# PG04_Communications.net
KiCad netlist of a schematic drawn in Altium Designer
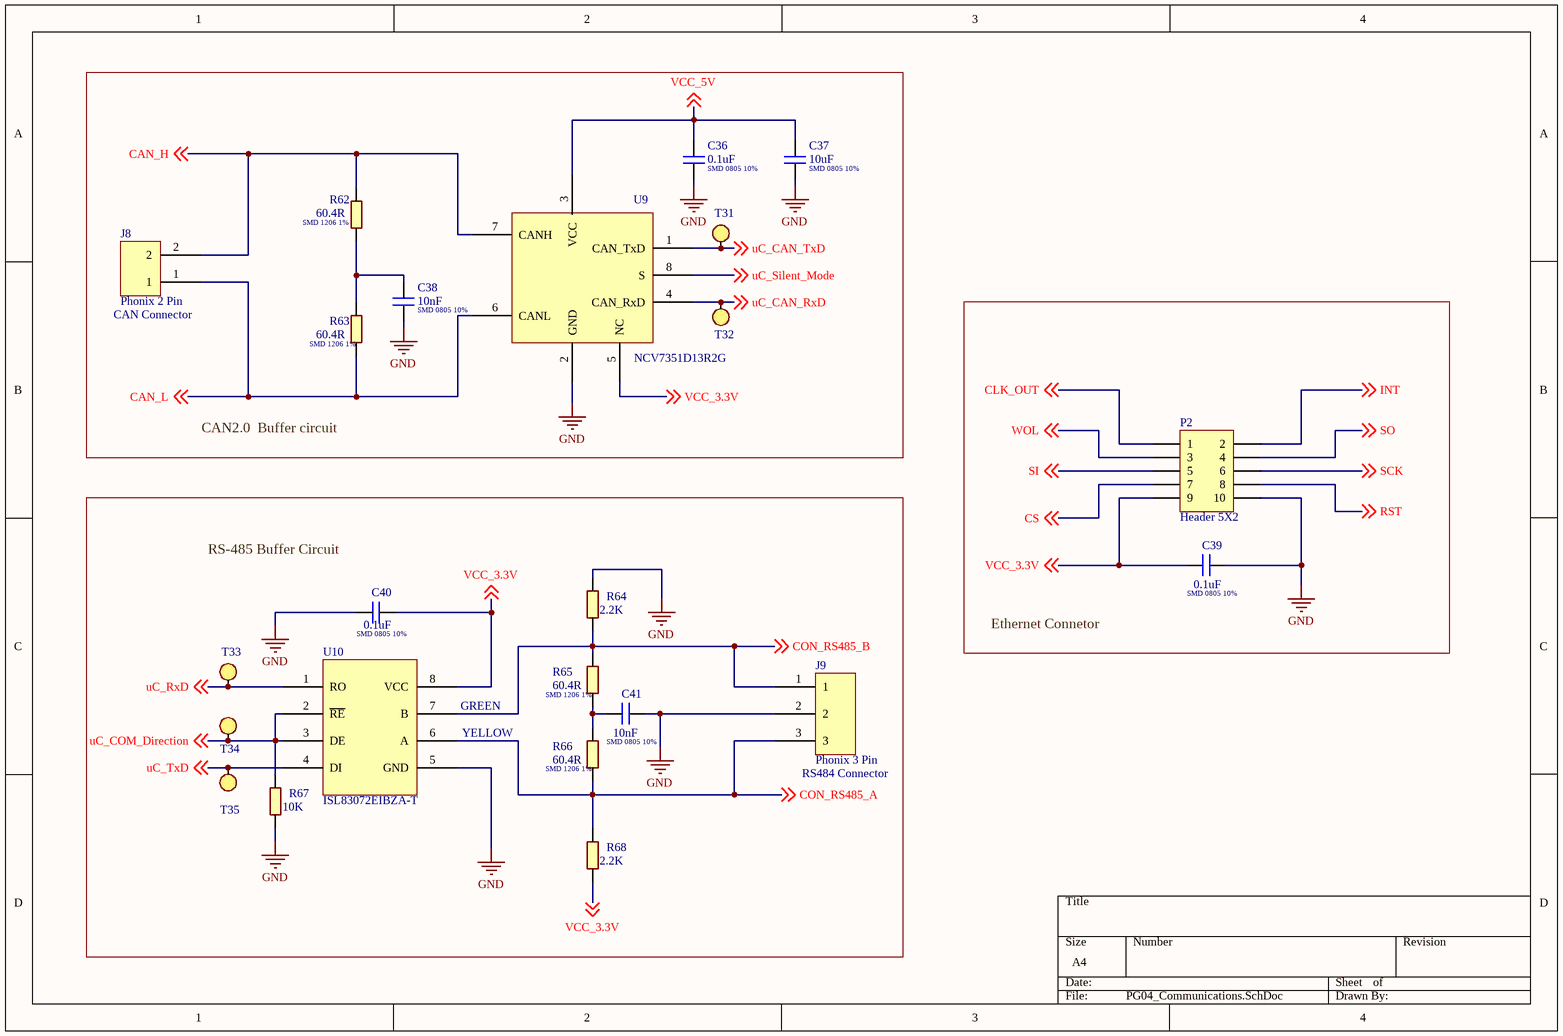
[diagram p0: PG04_Communications.SchDoc]

(export (version "E")
  (design (tool "Eeschema 10.0.6"))
  (components
    (comp (ref "C36")
      (value "SMD 0805 10%")
      (footprint "SMD0805")
      (fields (field (name "MANUFACTURER") "Vishay") (field (name "ALTIUM_VALUE") "0.1uF"))
      (libsource (lib "Schlib1") (part "CAP_SMD"))
    )
    (comp (ref "C37")
      (value "SMD 0805 10%")
      (footprint "SMD0805")
      (fields (field (name "MANUFACTURER") "Vishay") (field (name "ALTIUM_VALUE") "10uF"))
      (libsource (lib "Schlib1") (part "CAP_SMD"))
    )
    (comp (ref "C38")
      (value "SMD 0805 10%")
      (footprint "SMD0805")
      (fields (field (name "MANUFACTURER") "Vishay") (field (name "ALTIUM_VALUE") "10nF"))
      (libsource (lib "Schlib1") (part "CAP_SMD"))
    )
    (comp (ref "C39")
      (value "SMD 0805 10%")
      (footprint "SMD0805")
      (fields (field (name "MANUFACTURER") "Vishay") (field (name "ALTIUM_VALUE") "0.1uF"))
      (libsource (lib "Schlib1") (part "CAP_SMD"))
    )
    (comp (ref "C40")
      (value "SMD 0805 10%")
      (footprint "SMD0805")
      (fields (field (name "MANUFACTURER") "Vishay") (field (name "ALTIUM_VALUE") "0.1uF"))
      (libsource (lib "Schlib1") (part "CAP_SMD"))
    )
    (comp (ref "C41")
      (value "SMD 0805 10%")
      (footprint "SMD0805")
      (fields (field (name "MANUFACTURER") "Vishay") (field (name "ALTIUM_VALUE") "10nF"))
      (libsource (lib "Schlib1") (part "CAP_SMD"))
    )
    (comp (ref "J8")
      (value "Phonix 2 Pin")
      (footprint "PHONIX2")
      (libsource (lib "Schlib1") (part "Phonix_2_Pin"))
    )
    (comp (ref "J9")
      (value "Phonix 3 Pin")
      (footprint "Phonix_3")
      (libsource (lib "Schlib1") (part "Phonix_3_Pin"))
    )
    (comp (ref "P2")
      (value "Header 5X2")
      (footprint "HDR2X5")
      (description "Header, 5-Pin, Dual row")
      (fields (field (name "PUBLISHER") "Altium Limited"))
      (libsource (lib "Miscellaneous Connectors") (part "Header 5X2"))
    )
    (comp (ref "R62")
      (value "SMD 1206 1%")
      (footprint "SMD1206")
      (description "SMD1206  1% Resistor")
      (fields (field (name "MANUFACTURER") "Vishay") (field (name "ALTIUM_VALUE") "60.4R"))
      (libsource (lib "Schlib1") (part "RES_SMD"))
    )
    (comp (ref "R63")
      (value "SMD 1206 1%")
      (footprint "SMD1206")
      (description "SMD1206  1% Resistor")
      (fields (field (name "MANUFACTURER") "Vishay") (field (name "ALTIUM_VALUE") "60.4R"))
      (libsource (lib "Schlib1") (part "RES_SMD"))
    )
    (comp (ref "R64")
      (value "2.2K")
      (footprint "SMD1206")
      (description "SMD1206  1% Resistor")
      (fields (field (name "MANUFACTURER") "Vishay") (field (name "Comment") "SMD 1206 1%"))
      (libsource (lib "") (part "RES_SMD_1"))
    )
    (comp (ref "R65")
      (value "SMD 1206 1%")
      (footprint "SMD1206")
      (description "SMD1206  1% Resistor")
      (fields (field (name "MANUFACTURER") "Vishay") (field (name "ALTIUM_VALUE") "60.4R"))
      (libsource (lib "Schlib1") (part "RES_SMD"))
    )
    (comp (ref "R66")
      (value "SMD 1206 1%")
      (footprint "SMD1206")
      (description "SMD1206  1% Resistor")
      (fields (field (name "MANUFACTURER") "Vishay") (field (name "ALTIUM_VALUE") "60.4R"))
      (libsource (lib "Schlib1") (part "RES_SMD"))
    )
    (comp (ref "R67")
      (value "10K")
      (footprint "SMD1206")
      (description "SMD1206  1% Resistor")
      (fields (field (name "MANUFACTURER") "Vishay") (field (name "Comment") "SMD 1206 1%"))
      (libsource (lib "") (part "RES_SMD_1"))
    )
    (comp (ref "R68")
      (value "2.2K")
      (footprint "SMD1206")
      (description "SMD1206  1% Resistor")
      (fields (field (name "MANUFACTURER") "Vishay") (field (name "Comment") "SMD 1206 1%"))
      (libsource (lib "") (part "RES_SMD_1"))
    )
    (comp (ref "T31")
      (value "Through hole TestPoint")
      (footprint "TP")
      (libsource (lib "Schlib1") (part "TestPoint_TH"))
    )
    (comp (ref "T32")
      (value "Through hole TestPoint")
      (footprint "TP")
      (libsource (lib "") (part "TestPoint_TH_1"))
    )
    (comp (ref "T33")
      (value "Through hole TestPoint")
      (footprint "TP")
      (libsource (lib "Schlib1") (part "TestPoint_TH"))
    )
    (comp (ref "T34")
      (value "Through hole TestPoint")
      (footprint "TP")
      (libsource (lib "Schlib1") (part "TestPoint_TH"))
    )
    (comp (ref "T35")
      (value "Through hole TestPoint")
      (footprint "TP")
      (libsource (lib "") (part "TestPoint_TH_1"))
    )
    (comp (ref "U9")
      (value "NCV7351D13R2G")
      (footprint "SOIC-8")
      (fields (field (name "MANUFACTURER") "Onsemi") (field (name "Comment") "CAN Transciver"))
      (libsource (lib "Schlib1") (part "NCV7351"))
    )
    (comp (ref "U10")
      (value "ISL83072EIBZA-T")
      (footprint "SOIC-8")
      (fields (field (name "MANUFACTURER") "Maxim") (field (name "Comment") "MAX485"))
      (libsource (lib "Schlib1") (part "MAX485"))
    )
  )
  (nets
    (net (code "1") (name "CAN_H") (class "Default")
      (node (ref "J8") (pin "2") (pinfunction "2_2") (pintype "passive"))
      (node (ref "R62") (pin "1") (pinfunction "1_1") (pintype "passive"))
      (node (ref "U9") (pin "7") (pinfunction "CANH_7") (pintype "passive"))
    )
    (net (code "2") (name "CAN_L") (class "Default")
      (node (ref "J8") (pin "1") (pinfunction "1_1") (pintype "passive"))
      (node (ref "R63") (pin "2") (pinfunction "2_2") (pintype "passive"))
      (node (ref "U9") (pin "6") (pinfunction "CANL_6") (pintype "passive"))
    )
    (net (code "3") (name "CLK_OUT") (class "Default")
      (node (ref "P2") (pin "1") (pinfunction "1_1") (pintype "passive"))
    )
    (net (code "4") (name "CON_RS485_A") (class "Default")
      (node (ref "J9") (pin "3") (pinfunction "3_3") (pintype "passive"))
      (node (ref "R66") (pin "2") (pinfunction "2_2") (pintype "passive"))
      (node (ref "R68") (pin "2") (pinfunction "2_2") (pintype "passive"))
      (node (ref "U10") (pin "6") (pinfunction "A_6") (pintype "passive"))
    )
    (net (code "5") (name "CON_RS485_B") (class "Default")
      (node (ref "J9") (pin "1") (pinfunction "1_1") (pintype "passive"))
      (node (ref "R64") (pin "1") (pinfunction "1_1") (pintype "passive"))
      (node (ref "R65") (pin "1") (pinfunction "1_1") (pintype "passive"))
      (node (ref "U10") (pin "7") (pinfunction "B_7") (pintype "passive"))
    )
    (net (code "6") (name "CS") (class "Default")
      (node (ref "P2") (pin "7") (pinfunction "7_7") (pintype "passive"))
    )
    (net (code "7") (name "GND") (class "Default")
      (node (ref "C36") (pin "2") (pinfunction "2_2") (pintype "passive"))
      (node (ref "C37") (pin "2") (pinfunction "2_2") (pintype "passive"))
      (node (ref "C38") (pin "2") (pinfunction "2_2") (pintype "passive"))
      (node (ref "C39") (pin "2") (pinfunction "2_2") (pintype "passive"))
      (node (ref "C40") (pin "1") (pinfunction "1_1") (pintype "passive"))
      (node (ref "C41") (pin "2") (pinfunction "2_2") (pintype "passive"))
      (node (ref "J9") (pin "2") (pinfunction "2_2") (pintype "passive"))
      (node (ref "P2") (pin "10") (pinfunction "10_10") (pintype "passive"))
      (node (ref "R64") (pin "2") (pinfunction "2_2") (pintype "passive"))
      (node (ref "R67") (pin "1") (pinfunction "1_1") (pintype "passive"))
      (node (ref "U10") (pin "5") (pinfunction "GND_5") (pintype "passive"))
      (node (ref "U9") (pin "2") (pinfunction "GND_2") (pintype "passive"))
    )
    (net (code "8") (name "INT") (class "Default")
      (node (ref "P2") (pin "2") (pinfunction "2_2") (pintype "passive"))
    )
    (net (code "9") (name "Net-(C38-Pad1)") (class "Default")
      (node (ref "C38") (pin "1") (pinfunction "1_1") (pintype "passive"))
      (node (ref "R62") (pin "2") (pinfunction "2_2") (pintype "passive"))
      (node (ref "R63") (pin "1") (pinfunction "1_1") (pintype "passive"))
    )
    (net (code "10") (name "Net-(C41-Pad1)") (class "Default")
      (node (ref "C41") (pin "1") (pinfunction "1_1") (pintype "passive"))
      (node (ref "R65") (pin "2") (pinfunction "2_2") (pintype "passive"))
      (node (ref "R66") (pin "1") (pinfunction "1_1") (pintype "passive"))
    )
    (net (code "11") (name "RST") (class "Default")
      (node (ref "P2") (pin "8") (pinfunction "8_8") (pintype "passive"))
    )
    (net (code "12") (name "SCK") (class "Default")
      (node (ref "P2") (pin "6") (pinfunction "6_6") (pintype "passive"))
    )
    (net (code "13") (name "SI") (class "Default")
      (node (ref "P2") (pin "5") (pinfunction "5_5") (pintype "passive"))
    )
    (net (code "14") (name "SO") (class "Default")
      (node (ref "P2") (pin "4") (pinfunction "4_4") (pintype "passive"))
    )
    (net (code "15") (name "VCC_3.3V") (class "Default")
      (node (ref "C39") (pin "1") (pinfunction "1_1") (pintype "passive"))
      (node (ref "C40") (pin "2") (pinfunction "2_2") (pintype "passive"))
      (node (ref "P2") (pin "9") (pinfunction "9_9") (pintype "passive"))
      (node (ref "R68") (pin "1") (pinfunction "1_1") (pintype "passive"))
      (node (ref "U10") (pin "8") (pinfunction "VCC_8") (pintype "passive"))
      (node (ref "U9") (pin "5") (pinfunction "NC_5") (pintype "passive"))
    )
    (net (code "16") (name "VCC_5V") (class "Default")
      (node (ref "C36") (pin "1") (pinfunction "1_1") (pintype "passive"))
      (node (ref "C37") (pin "1") (pinfunction "1_1") (pintype "passive"))
      (node (ref "U9") (pin "3") (pinfunction "VCC_3") (pintype "passive"))
    )
    (net (code "17") (name "WOL") (class "Default")
      (node (ref "P2") (pin "3") (pinfunction "3_3") (pintype "passive"))
    )
    (net (code "18") (name "uC_CAN_RxD") (class "Default")
      (node (ref "T32") (pin "1") (pintype "passive"))
      (node (ref "U9") (pin "4") (pinfunction "CAN_RxD_4") (pintype "passive"))
    )
    (net (code "19") (name "uC_CAN_TxD") (class "Default")
      (node (ref "T31") (pin "1") (pintype "passive"))
      (node (ref "U9") (pin "1") (pinfunction "CAN_TxD_1") (pintype "passive"))
    )
    (net (code "20") (name "uC_COM_Direction") (class "Default")
      (node (ref "R67") (pin "2") (pinfunction "2_2") (pintype "passive"))
      (node (ref "T34") (pin "1") (pintype "passive"))
      (node (ref "U10") (pin "2") (pinfunction "~{RE}_2") (pintype "passive"))
      (node (ref "U10") (pin "3") (pinfunction "DE_3") (pintype "passive"))
    )
    (net (code "21") (name "uC_RxD") (class "Default")
      (node (ref "T33") (pin "1") (pintype "passive"))
      (node (ref "U10") (pin "1") (pinfunction "RO_1") (pintype "passive"))
    )
    (net (code "22") (name "uC_Silent_Mode") (class "Default")
      (node (ref "U9") (pin "8") (pinfunction "S_8") (pintype "passive"))
    )
    (net (code "23") (name "uC_TxD") (class "Default")
      (node (ref "T35") (pin "1") (pintype "passive"))
      (node (ref "U10") (pin "4") (pinfunction "DI_4") (pintype "passive"))
    )
  )
)
